# TaSCUD_ver02.net
KiCad netlist of a schematic drawn in EAGLE
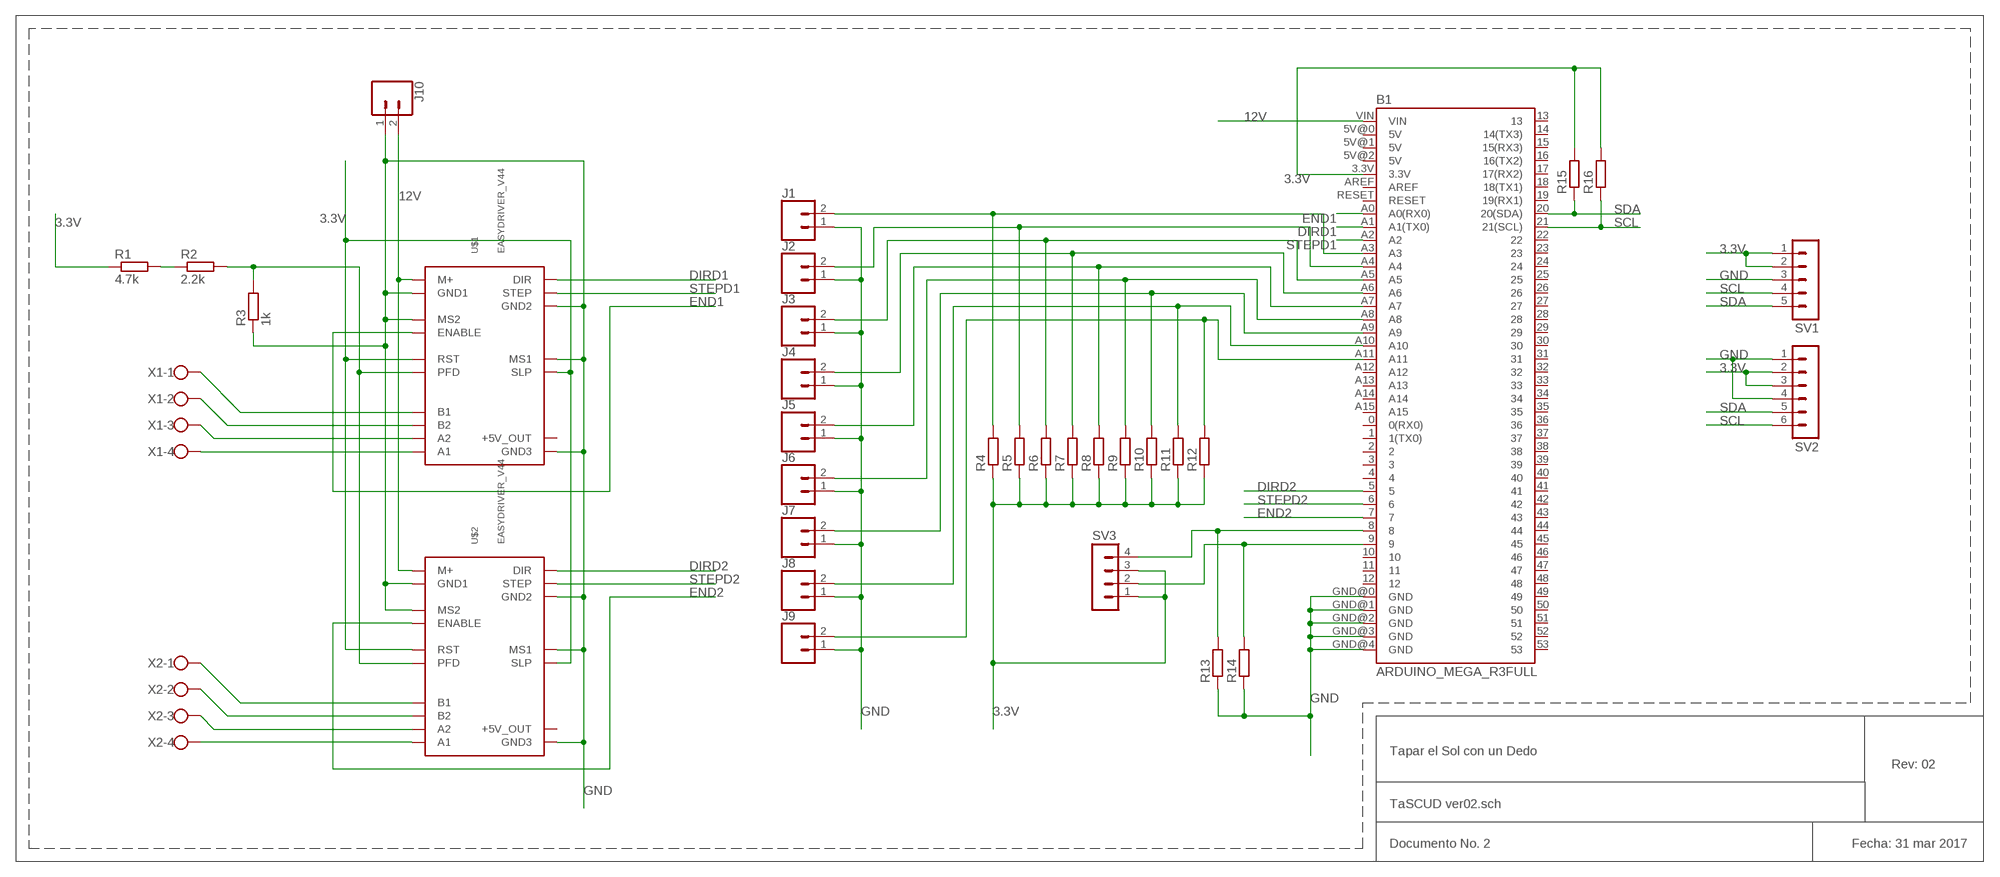
[diagram p0: schematic, sheet 1]

(export (version "E")
  (design (tool "Eeschema 10.0.6"))
  (components
    (comp (ref "B1")
      (value "ARDUINO_MEGA_R3FULL")
      (footprint "eagle-import:ARDUINO_MEGA")
      (libsource (lib "eagle-import") (part "ARDUINO_MEGA_R3FULL"))
    )
    (comp (ref "J1")
      (value "CONN_023.5MM-NO_SILK")
      (footprint "eagle-import:SCREWTERMINAL-3.5MM-2-NS")
      (libsource (lib "eagle-import") (part "CONN_023.5MM-NO_SILK"))
    )
    (comp (ref "J2")
      (value "CONN_023.5MM-NO_SILK")
      (footprint "eagle-import:SCREWTERMINAL-3.5MM-2-NS")
      (libsource (lib "eagle-import") (part "CONN_023.5MM-NO_SILK"))
    )
    (comp (ref "J3")
      (value "CONN_023.5MM-NO_SILK")
      (footprint "eagle-import:SCREWTERMINAL-3.5MM-2-NS")
      (libsource (lib "eagle-import") (part "CONN_023.5MM-NO_SILK"))
    )
    (comp (ref "J4")
      (value "CONN_023.5MM-NO_SILK")
      (footprint "eagle-import:SCREWTERMINAL-3.5MM-2-NS")
      (libsource (lib "eagle-import") (part "CONN_023.5MM-NO_SILK"))
    )
    (comp (ref "J5")
      (value "CONN_023.5MM-NO_SILK")
      (footprint "eagle-import:SCREWTERMINAL-3.5MM-2-NS")
      (libsource (lib "eagle-import") (part "CONN_023.5MM-NO_SILK"))
    )
    (comp (ref "J6")
      (value "CONN_023.5MM-NO_SILK")
      (footprint "eagle-import:SCREWTERMINAL-3.5MM-2-NS")
      (libsource (lib "eagle-import") (part "CONN_023.5MM-NO_SILK"))
    )
    (comp (ref "J7")
      (value "CONN_023.5MM-NO_SILK")
      (footprint "eagle-import:SCREWTERMINAL-3.5MM-2-NS")
      (libsource (lib "eagle-import") (part "CONN_023.5MM-NO_SILK"))
    )
    (comp (ref "J8")
      (value "CONN_023.5MM-NO_SILK")
      (footprint "eagle-import:SCREWTERMINAL-3.5MM-2-NS")
      (libsource (lib "eagle-import") (part "CONN_023.5MM-NO_SILK"))
    )
    (comp (ref "J9")
      (value "CONN_023.5MM-NO_SILK")
      (footprint "eagle-import:SCREWTERMINAL-3.5MM-2-NS")
      (libsource (lib "eagle-import") (part "CONN_023.5MM-NO_SILK"))
    )
    (comp (ref "J10")
      (value "CONN_023.5MM-NO_SILK")
      (footprint "eagle-import:SCREWTERMINAL-3.5MM-2-NS")
      (libsource (lib "eagle-import") (part "CONN_023.5MM-NO_SILK"))
    )
    (comp (ref "R1")
      (value "4.7k")
      (footprint "eagle-import:0204_7")
      (libsource (lib "eagle-import") (part "R-EU_0204/7"))
    )
    (comp (ref "R2")
      (value "2.2k")
      (footprint "eagle-import:0204_7")
      (libsource (lib "eagle-import") (part "R-EU_0204/7"))
    )
    (comp (ref "R3")
      (value "1k")
      (footprint "eagle-import:0204_7")
      (libsource (lib "eagle-import") (part "R-EU_0204/7"))
    )
    (comp (ref "R4")
      (value "R-EU_0204/7")
      (footprint "eagle-import:0204_7")
      (libsource (lib "eagle-import") (part "R-EU_0204/7"))
    )
    (comp (ref "R5")
      (value "R-EU_0204/7")
      (footprint "eagle-import:0204_7")
      (libsource (lib "eagle-import") (part "R-EU_0204/7"))
    )
    (comp (ref "R6")
      (value "R-EU_0204/7")
      (footprint "eagle-import:0204_7")
      (libsource (lib "eagle-import") (part "R-EU_0204/7"))
    )
    (comp (ref "R7")
      (value "R-EU_0204/7")
      (footprint "eagle-import:0204_7")
      (libsource (lib "eagle-import") (part "R-EU_0204/7"))
    )
    (comp (ref "R8")
      (value "R-EU_0204/7")
      (footprint "eagle-import:0204_7")
      (libsource (lib "eagle-import") (part "R-EU_0204/7"))
    )
    (comp (ref "R9")
      (value "R-EU_0204/7")
      (footprint "eagle-import:0204_7")
      (libsource (lib "eagle-import") (part "R-EU_0204/7"))
    )
    (comp (ref "R10")
      (value "R-EU_0204/7")
      (footprint "eagle-import:0204_7")
      (libsource (lib "eagle-import") (part "R-EU_0204/7"))
    )
    (comp (ref "R11")
      (value "R-EU_0204/7")
      (footprint "eagle-import:0204_7")
      (libsource (lib "eagle-import") (part "R-EU_0204/7"))
    )
    (comp (ref "R12")
      (value "R-EU_0204/7")
      (footprint "eagle-import:0204_7")
      (libsource (lib "eagle-import") (part "R-EU_0204/7"))
    )
    (comp (ref "R13")
      (value "R-EU_0204/7")
      (footprint "eagle-import:0204_7")
      (libsource (lib "eagle-import") (part "R-EU_0204/7"))
    )
    (comp (ref "R14")
      (value "R-EU_0204/7")
      (footprint "eagle-import:0204_7")
      (libsource (lib "eagle-import") (part "R-EU_0204/7"))
    )
    (comp (ref "R15")
      (value "R-EU_0204/7")
      (footprint "eagle-import:0204_7")
      (libsource (lib "eagle-import") (part "R-EU_0204/7"))
    )
    (comp (ref "R16")
      (value "R-EU_0204/7")
      (footprint "eagle-import:0204_7")
      (libsource (lib "eagle-import") (part "R-EU_0204/7"))
    )
    (comp (ref "SV1")
      (value "MA05-1")
      (footprint "eagle-import:MA05-1")
      (libsource (lib "eagle-import") (part "MA05-1"))
    )
    (comp (ref "SV2")
      (value "MA06-1")
      (footprint "eagle-import:MA06-1")
      (libsource (lib "eagle-import") (part "MA06-1"))
    )
    (comp (ref "SV3")
      (value "MA04-1")
      (footprint "eagle-import:MA04-1")
      (libsource (lib "eagle-import") (part "MA04-1"))
    )
    (comp (ref "U$1")
      (value "EASYDRIVER_V44")
      (footprint "eagle-import:EASYDRIVER_V44")
      (libsource (lib "eagle-import") (part "EASYDRIVER_V44"))
    )
    (comp (ref "U$2")
      (value "EASYDRIVER_V44")
      (footprint "eagle-import:EASYDRIVER_V44")
      (libsource (lib "eagle-import") (part "EASYDRIVER_V44"))
    )
    (comp (ref "X1")
      (value "W237-4")
      (footprint "eagle-import:W237-4")
      (libsource (lib "eagle-import") (part "W237-4"))
    )
    (comp (ref "X2")
      (value "W237-4")
      (footprint "eagle-import:W237-4")
      (libsource (lib "eagle-import") (part "W237-4"))
    )
  )
  (nets
    (net (code "1") (name "/3.3V") (class "Default")
      (node (ref "B1") (pin "3.3V") (pinfunction "3.3V_3.3V") (pintype "bidirectional"))
      (node (ref "R1") (pin "1") (pinfunction "1_1") (pintype "passive"))
      (node (ref "R10") (pin "1") (pinfunction "1_1") (pintype "passive"))
      (node (ref "R11") (pin "1") (pinfunction "1_1") (pintype "passive"))
      (node (ref "R12") (pin "1") (pinfunction "1_1") (pintype "passive"))
      (node (ref "R15") (pin "2") (pinfunction "2_2") (pintype "passive"))
      (node (ref "R16") (pin "2") (pinfunction "2_2") (pintype "passive"))
      (node (ref "R4") (pin "1") (pinfunction "1_1") (pintype "passive"))
      (node (ref "R5") (pin "1") (pinfunction "1_1") (pintype "passive"))
      (node (ref "R6") (pin "1") (pinfunction "1_1") (pintype "passive"))
      (node (ref "R7") (pin "1") (pinfunction "1_1") (pintype "passive"))
      (node (ref "R8") (pin "1") (pinfunction "1_1") (pintype "passive"))
      (node (ref "R9") (pin "1") (pinfunction "1_1") (pintype "passive"))
      (node (ref "SV1") (pin "1") (pinfunction "1_1") (pintype "passive"))
      (node (ref "SV1") (pin "2") (pinfunction "2_2") (pintype "passive"))
      (node (ref "SV2") (pin "2") (pinfunction "2_2") (pintype "passive"))
      (node (ref "SV2") (pin "3") (pinfunction "3_3") (pintype "passive"))
      (node (ref "SV3") (pin "1") (pinfunction "1_1") (pintype "passive"))
      (node (ref "SV3") (pin "3") (pinfunction "3_3") (pintype "passive"))
      (node (ref "U$1") (pin "RST") (pinfunction "RST_RST") (pintype "bidirectional"))
      (node (ref "U$1") (pin "SLEEP") (pinfunction "SLP_SLEEP") (pintype "bidirectional"))
      (node (ref "U$2") (pin "RST") (pinfunction "RST_RST") (pintype "bidirectional"))
      (node (ref "U$2") (pin "SLEEP") (pinfunction "SLP_SLEEP") (pintype "bidirectional"))
    )
    (net (code "2") (name "/12V") (class "Default")
      (node (ref "B1") (pin "VIN") (pinfunction "VIN_VIN") (pintype "bidirectional"))
      (node (ref "J10") (pin "2") (pinfunction "2_2") (pintype "passive"))
      (node (ref "U$1") (pin "M+") (pinfunction "M+_M+") (pintype "bidirectional"))
      (node (ref "U$2") (pin "M+") (pinfunction "M+_M+") (pintype "bidirectional"))
    )
    (net (code "3") (name "/DIRD1") (class "Default")
      (node (ref "B1") (pin "A1") (pinfunction "A1(TX0)_A1") (pintype "bidirectional"))
      (node (ref "U$1") (pin "DIR") (pinfunction "DIR_DIR") (pintype "bidirectional"))
    )
    (net (code "4") (name "/DIRD2") (class "Default")
      (node (ref "B1") (pin "5") (pinfunction "5_5") (pintype "bidirectional"))
      (node (ref "U$2") (pin "DIR") (pinfunction "DIR_DIR") (pintype "bidirectional"))
    )
    (net (code "5") (name "/END1") (class "Default")
      (node (ref "B1") (pin "A0") (pinfunction "A0(RX0)_A0") (pintype "bidirectional"))
      (node (ref "U$1") (pin "ENABLE") (pinfunction "ENABLE_ENABLE") (pintype "bidirectional"))
    )
    (net (code "6") (name "/END2") (class "Default")
      (node (ref "B1") (pin "7") (pinfunction "7_7") (pintype "bidirectional"))
      (node (ref "U$2") (pin "ENABLE") (pinfunction "ENABLE_ENABLE") (pintype "bidirectional"))
    )
    (net (code "7") (name "/GND") (class "Default")
      (node (ref "B1") (pin "GND@0") (pinfunction "GND_GND@0") (pintype "bidirectional"))
      (node (ref "B1") (pin "GND@1") (pinfunction "GND_GND@1") (pintype "bidirectional"))
      (node (ref "B1") (pin "GND@2") (pinfunction "GND_GND@2") (pintype "bidirectional"))
      (node (ref "B1") (pin "GND@3") (pinfunction "GND_GND@3") (pintype "bidirectional"))
      (node (ref "B1") (pin "GND@4") (pinfunction "GND_GND@4") (pintype "bidirectional"))
      (node (ref "J1") (pin "1") (pinfunction "1_1") (pintype "passive"))
      (node (ref "J10") (pin "1") (pinfunction "1_1") (pintype "passive"))
      (node (ref "J2") (pin "1") (pinfunction "1_1") (pintype "passive"))
      (node (ref "J3") (pin "1") (pinfunction "1_1") (pintype "passive"))
      (node (ref "J4") (pin "1") (pinfunction "1_1") (pintype "passive"))
      (node (ref "J5") (pin "1") (pinfunction "1_1") (pintype "passive"))
      (node (ref "J6") (pin "1") (pinfunction "1_1") (pintype "passive"))
      (node (ref "J7") (pin "1") (pinfunction "1_1") (pintype "passive"))
      (node (ref "J8") (pin "1") (pinfunction "1_1") (pintype "passive"))
      (node (ref "J9") (pin "1") (pinfunction "1_1") (pintype "passive"))
      (node (ref "R13") (pin "1") (pinfunction "1_1") (pintype "passive"))
      (node (ref "R14") (pin "1") (pinfunction "1_1") (pintype "passive"))
      (node (ref "R3") (pin "1") (pinfunction "1_1") (pintype "passive"))
      (node (ref "SV1") (pin "3") (pinfunction "3_3") (pintype "passive"))
      (node (ref "SV2") (pin "1") (pinfunction "1_1") (pintype "passive"))
      (node (ref "SV2") (pin "4") (pinfunction "4_4") (pintype "passive"))
      (node (ref "U$1") (pin "GND1") (pinfunction "GND1_GND1") (pintype "bidirectional"))
      (node (ref "U$1") (pin "GND2") (pinfunction "GND2_GND2") (pintype "bidirectional"))
      (node (ref "U$1") (pin "GND3") (pinfunction "GND3_GND3") (pintype "bidirectional"))
      (node (ref "U$1") (pin "MS1") (pinfunction "MS1_MS1") (pintype "bidirectional"))
      (node (ref "U$1") (pin "MS2") (pinfunction "MS2_MS2") (pintype "bidirectional"))
      (node (ref "U$2") (pin "GND1") (pinfunction "GND1_GND1") (pintype "bidirectional"))
      (node (ref "U$2") (pin "GND2") (pinfunction "GND2_GND2") (pintype "bidirectional"))
      (node (ref "U$2") (pin "GND3") (pinfunction "GND3_GND3") (pintype "bidirectional"))
      (node (ref "U$2") (pin "MS1") (pinfunction "MS1_MS1") (pintype "bidirectional"))
      (node (ref "U$2") (pin "MS2") (pinfunction "MS2_MS2") (pintype "bidirectional"))
    )
    (net (code "8") (name "/SCL") (class "Default")
      (node (ref "B1") (pin "21") (pinfunction "21(SCL)_21") (pintype "bidirectional"))
      (node (ref "R16") (pin "1") (pinfunction "1_1") (pintype "passive"))
      (node (ref "SV1") (pin "4") (pinfunction "4_4") (pintype "passive"))
      (node (ref "SV2") (pin "6") (pinfunction "6_6") (pintype "passive"))
    )
    (net (code "9") (name "/SDA") (class "Default")
      (node (ref "B1") (pin "20") (pinfunction "20(SDA)_20") (pintype "bidirectional"))
      (node (ref "R15") (pin "1") (pinfunction "1_1") (pintype "passive"))
      (node (ref "SV1") (pin "5") (pinfunction "5_5") (pintype "passive"))
      (node (ref "SV2") (pin "5") (pinfunction "5_5") (pintype "passive"))
    )
    (net (code "10") (name "/STEPD1") (class "Default")
      (node (ref "B1") (pin "A2") (pinfunction "A2_A2") (pintype "bidirectional"))
      (node (ref "U$1") (pin "STEP") (pinfunction "STEP_STEP") (pintype "bidirectional"))
    )
    (net (code "11") (name "/STEPD2") (class "Default")
      (node (ref "B1") (pin "6") (pinfunction "6_6") (pintype "bidirectional"))
      (node (ref "U$2") (pin "STEP") (pinfunction "STEP_STEP") (pintype "bidirectional"))
    )
    (net (code "12") (name "Net-(B1-Pad8)") (class "Default")
      (node (ref "B1") (pin "8") (pinfunction "8_8") (pintype "bidirectional"))
      (node (ref "R13") (pin "2") (pinfunction "2_2") (pintype "passive"))
      (node (ref "SV3") (pin "4") (pinfunction "4_4") (pintype "passive"))
    )
    (net (code "13") (name "Net-(B1-Pad9)") (class "Default")
      (node (ref "B1") (pin "9") (pinfunction "9_9") (pintype "bidirectional"))
      (node (ref "R14") (pin "2") (pinfunction "2_2") (pintype "passive"))
      (node (ref "SV3") (pin "2") (pinfunction "2_2") (pintype "passive"))
    )
    (net (code "14") (name "Net-(B1-PadA3)") (class "Default")
      (node (ref "B1") (pin "A3") (pinfunction "A3_A3") (pintype "bidirectional"))
      (node (ref "J1") (pin "2") (pinfunction "2_2") (pintype "passive"))
      (node (ref "R4") (pin "2") (pinfunction "2_2") (pintype "passive"))
    )
    (net (code "15") (name "Net-(B1-PadA4)") (class "Default")
      (node (ref "B1") (pin "A4") (pinfunction "A4_A4") (pintype "bidirectional"))
      (node (ref "J2") (pin "2") (pinfunction "2_2") (pintype "passive"))
      (node (ref "R5") (pin "2") (pinfunction "2_2") (pintype "passive"))
    )
    (net (code "16") (name "Net-(B1-PadA5)") (class "Default")
      (node (ref "B1") (pin "A5") (pinfunction "A5_A5") (pintype "bidirectional"))
      (node (ref "J3") (pin "2") (pinfunction "2_2") (pintype "passive"))
      (node (ref "R6") (pin "2") (pinfunction "2_2") (pintype "passive"))
    )
    (net (code "17") (name "Net-(B1-PadA6)") (class "Default")
      (node (ref "B1") (pin "A6") (pinfunction "A6_A6") (pintype "bidirectional"))
      (node (ref "J4") (pin "2") (pinfunction "2_2") (pintype "passive"))
      (node (ref "R7") (pin "2") (pinfunction "2_2") (pintype "passive"))
    )
    (net (code "18") (name "Net-(B1-PadA7)") (class "Default")
      (node (ref "B1") (pin "A7") (pinfunction "A7_A7") (pintype "bidirectional"))
      (node (ref "J5") (pin "2") (pinfunction "2_2") (pintype "passive"))
      (node (ref "R8") (pin "2") (pinfunction "2_2") (pintype "passive"))
    )
    (net (code "19") (name "Net-(B1-PadA8)") (class "Default")
      (node (ref "B1") (pin "A8") (pinfunction "A8_A8") (pintype "bidirectional"))
      (node (ref "J6") (pin "2") (pinfunction "2_2") (pintype "passive"))
      (node (ref "R9") (pin "2") (pinfunction "2_2") (pintype "passive"))
    )
    (net (code "20") (name "Net-(B1-PadA9)") (class "Default")
      (node (ref "B1") (pin "A9") (pinfunction "A9_A9") (pintype "bidirectional"))
      (node (ref "J7") (pin "2") (pinfunction "2_2") (pintype "passive"))
      (node (ref "R10") (pin "2") (pinfunction "2_2") (pintype "passive"))
    )
    (net (code "21") (name "Net-(B1-PadA10)") (class "Default")
      (node (ref "B1") (pin "A10") (pinfunction "A10_A10") (pintype "bidirectional"))
      (node (ref "J8") (pin "2") (pinfunction "2_2") (pintype "passive"))
      (node (ref "R11") (pin "2") (pinfunction "2_2") (pintype "passive"))
    )
    (net (code "22") (name "Net-(B1-PadA11)") (class "Default")
      (node (ref "B1") (pin "A11") (pinfunction "A11_A11") (pintype "bidirectional"))
      (node (ref "J9") (pin "2") (pinfunction "2_2") (pintype "passive"))
      (node (ref "R12") (pin "2") (pinfunction "2_2") (pintype "passive"))
    )
    (net (code "23") (name "Net-(R1-Pad2)") (class "Default")
      (node (ref "R1") (pin "2") (pinfunction "2_2") (pintype "passive"))
      (node (ref "R2") (pin "1") (pinfunction "1_1") (pintype "passive"))
    )
    (net (code "24") (name "Net-(R2-Pad2)") (class "Default")
      (node (ref "R2") (pin "2") (pinfunction "2_2") (pintype "passive"))
      (node (ref "R3") (pin "2") (pinfunction "2_2") (pintype "passive"))
      (node (ref "U$1") (pin "PFD") (pinfunction "PFD_PFD") (pintype "bidirectional"))
      (node (ref "U$2") (pin "PFD") (pinfunction "PFD_PFD") (pintype "bidirectional"))
    )
    (net (code "25") (name "Net-(X1A-KL)") (class "Default")
      (node (ref "U$1") (pin "B1") (pinfunction "B1_B1") (pintype "bidirectional"))
      (node (ref "X1") (pin "1") (pinfunction "KL_1") (pintype "passive"))
    )
    (net (code "26") (name "Net-(X1B-KL)") (class "Default")
      (node (ref "U$1") (pin "B2") (pinfunction "B2_B2") (pintype "bidirectional"))
      (node (ref "X1") (pin "2") (pinfunction "KL_2") (pintype "passive"))
    )
    (net (code "27") (name "Net-(X1C-KL)") (class "Default")
      (node (ref "U$1") (pin "A2") (pinfunction "A2_A2") (pintype "bidirectional"))
      (node (ref "X1") (pin "3") (pinfunction "KL_3") (pintype "passive"))
    )
    (net (code "28") (name "Net-(X1D-KL)") (class "Default")
      (node (ref "U$1") (pin "A1") (pinfunction "A1_A1") (pintype "bidirectional"))
      (node (ref "X1") (pin "4") (pinfunction "KL_4") (pintype "passive"))
    )
    (net (code "29") (name "Net-(X2A-KL)") (class "Default")
      (node (ref "U$2") (pin "B1") (pinfunction "B1_B1") (pintype "bidirectional"))
      (node (ref "X2") (pin "1") (pinfunction "KL_1") (pintype "passive"))
    )
    (net (code "30") (name "Net-(X2B-KL)") (class "Default")
      (node (ref "U$2") (pin "B2") (pinfunction "B2_B2") (pintype "bidirectional"))
      (node (ref "X2") (pin "2") (pinfunction "KL_2") (pintype "passive"))
    )
    (net (code "31") (name "Net-(X2C-KL)") (class "Default")
      (node (ref "U$2") (pin "A2") (pinfunction "A2_A2") (pintype "bidirectional"))
      (node (ref "X2") (pin "3") (pinfunction "KL_3") (pintype "passive"))
    )
    (net (code "32") (name "Net-(X2D-KL)") (class "Default")
      (node (ref "U$2") (pin "A1") (pinfunction "A1_A1") (pintype "bidirectional"))
      (node (ref "X2") (pin "4") (pinfunction "KL_4") (pintype "passive"))
    )
    (net (code "33") (name "unconnected-(B1-0(RX0)-Pad0)") (class "Default")
      (node (ref "B1") (pin "0") (pinfunction "0(RX0)_0") (pintype "bidirectional"))
    )
    (net (code "34") (name "unconnected-(B1-1(TX0)-Pad1)") (class "Default")
      (node (ref "B1") (pin "1") (pinfunction "1(TX0)_1") (pintype "bidirectional"))
    )
    (net (code "35") (name "unconnected-(B1-5V-Pad5V@0)") (class "Default")
      (node (ref "B1") (pin "5V@0") (pinfunction "5V_5V@0") (pintype "bidirectional"))
    )
    (net (code "36") (name "unconnected-(B1-5V-Pad5V@1)") (class "Default")
      (node (ref "B1") (pin "5V@1") (pinfunction "5V_5V@1") (pintype "bidirectional"))
    )
    (net (code "37") (name "unconnected-(B1-5V-Pad5V@2)") (class "Default")
      (node (ref "B1") (pin "5V@2") (pinfunction "5V_5V@2") (pintype "bidirectional"))
    )
    (net (code "38") (name "unconnected-(B1-14(TX3)-Pad14)") (class "Default")
      (node (ref "B1") (pin "14") (pinfunction "14(TX3)_14") (pintype "bidirectional"))
    )
    (net (code "39") (name "unconnected-(B1-15(RX3)-Pad15)") (class "Default")
      (node (ref "B1") (pin "15") (pinfunction "15(RX3)_15") (pintype "bidirectional"))
    )
    (net (code "40") (name "unconnected-(B1-16(TX2)-Pad16)") (class "Default")
      (node (ref "B1") (pin "16") (pinfunction "16(TX2)_16") (pintype "bidirectional"))
    )
    (net (code "41") (name "unconnected-(B1-17(RX2)-Pad17)") (class "Default")
      (node (ref "B1") (pin "17") (pinfunction "17(RX2)_17") (pintype "bidirectional"))
    )
    (net (code "42") (name "unconnected-(B1-18(TX1)-Pad18)") (class "Default")
      (node (ref "B1") (pin "18") (pinfunction "18(TX1)_18") (pintype "bidirectional"))
    )
    (net (code "43") (name "unconnected-(B1-19(RX1)-Pad19)") (class "Default")
      (node (ref "B1") (pin "19") (pinfunction "19(RX1)_19") (pintype "bidirectional"))
    )
    (net (code "44") (name "unconnected-(B1-Pad2)") (class "Default")
      (node (ref "B1") (pin "2") (pinfunction "2_2") (pintype "bidirectional"))
    )
    (net (code "45") (name "unconnected-(B1-Pad3)") (class "Default")
      (node (ref "B1") (pin "3") (pinfunction "3_3") (pintype "bidirectional"))
    )
    (net (code "46") (name "unconnected-(B1-Pad4)") (class "Default")
      (node (ref "B1") (pin "4") (pinfunction "4_4") (pintype "bidirectional"))
    )
    (net (code "47") (name "unconnected-(B1-Pad10)") (class "Default")
      (node (ref "B1") (pin "10") (pinfunction "10_10") (pintype "bidirectional"))
    )
    (net (code "48") (name "unconnected-(B1-Pad11)") (class "Default")
      (node (ref "B1") (pin "11") (pinfunction "11_11") (pintype "bidirectional"))
    )
    (net (code "49") (name "unconnected-(B1-Pad12)") (class "Default")
      (node (ref "B1") (pin "12") (pinfunction "12_12") (pintype "bidirectional"))
    )
    (net (code "50") (name "unconnected-(B1-Pad13)") (class "Default")
      (node (ref "B1") (pin "13") (pinfunction "13_13") (pintype "bidirectional"))
    )
    (net (code "51") (name "unconnected-(B1-Pad22)") (class "Default")
      (node (ref "B1") (pin "22") (pinfunction "22_22") (pintype "bidirectional"))
    )
    (net (code "52") (name "unconnected-(B1-Pad23)") (class "Default")
      (node (ref "B1") (pin "23") (pinfunction "23_23") (pintype "bidirectional"))
    )
    (net (code "53") (name "unconnected-(B1-Pad24)") (class "Default")
      (node (ref "B1") (pin "24") (pinfunction "24_24") (pintype "bidirectional"))
    )
    (net (code "54") (name "unconnected-(B1-Pad25)") (class "Default")
      (node (ref "B1") (pin "25") (pinfunction "25_25") (pintype "bidirectional"))
    )
    (net (code "55") (name "unconnected-(B1-Pad26)") (class "Default")
      (node (ref "B1") (pin "26") (pinfunction "26_26") (pintype "bidirectional"))
    )
    (net (code "56") (name "unconnected-(B1-Pad27)") (class "Default")
      (node (ref "B1") (pin "27") (pinfunction "27_27") (pintype "bidirectional"))
    )
    (net (code "57") (name "unconnected-(B1-Pad28)") (class "Default")
      (node (ref "B1") (pin "28") (pinfunction "28_28") (pintype "bidirectional"))
    )
    (net (code "58") (name "unconnected-(B1-Pad29)") (class "Default")
      (node (ref "B1") (pin "29") (pinfunction "29_29") (pintype "bidirectional"))
    )
    (net (code "59") (name "unconnected-(B1-Pad30)") (class "Default")
      (node (ref "B1") (pin "30") (pinfunction "30_30") (pintype "bidirectional"))
    )
    (net (code "60") (name "unconnected-(B1-Pad31)") (class "Default")
      (node (ref "B1") (pin "31") (pinfunction "31_31") (pintype "bidirectional"))
    )
    (net (code "61") (name "unconnected-(B1-Pad32)") (class "Default")
      (node (ref "B1") (pin "32") (pinfunction "32_32") (pintype "bidirectional"))
    )
    (net (code "62") (name "unconnected-(B1-Pad33)") (class "Default")
      (node (ref "B1") (pin "33") (pinfunction "33_33") (pintype "bidirectional"))
    )
    (net (code "63") (name "unconnected-(B1-Pad34)") (class "Default")
      (node (ref "B1") (pin "34") (pinfunction "34_34") (pintype "bidirectional"))
    )
    (net (code "64") (name "unconnected-(B1-Pad35)") (class "Default")
      (node (ref "B1") (pin "35") (pinfunction "35_35") (pintype "bidirectional"))
    )
    (net (code "65") (name "unconnected-(B1-Pad36)") (class "Default")
      (node (ref "B1") (pin "36") (pinfunction "36_36") (pintype "bidirectional"))
    )
    (net (code "66") (name "unconnected-(B1-Pad37)") (class "Default")
      (node (ref "B1") (pin "37") (pinfunction "37_37") (pintype "bidirectional"))
    )
    (net (code "67") (name "unconnected-(B1-Pad38)") (class "Default")
      (node (ref "B1") (pin "38") (pinfunction "38_38") (pintype "bidirectional"))
    )
    (net (code "68") (name "unconnected-(B1-Pad39)") (class "Default")
      (node (ref "B1") (pin "39") (pinfunction "39_39") (pintype "bidirectional"))
    )
    (net (code "69") (name "unconnected-(B1-Pad40)") (class "Default")
      (node (ref "B1") (pin "40") (pinfunction "40_40") (pintype "bidirectional"))
    )
    (net (code "70") (name "unconnected-(B1-Pad41)") (class "Default")
      (node (ref "B1") (pin "41") (pinfunction "41_41") (pintype "bidirectional"))
    )
    (net (code "71") (name "unconnected-(B1-Pad42)") (class "Default")
      (node (ref "B1") (pin "42") (pinfunction "42_42") (pintype "bidirectional"))
    )
    (net (code "72") (name "unconnected-(B1-Pad43)") (class "Default")
      (node (ref "B1") (pin "43") (pinfunction "43_43") (pintype "bidirectional"))
    )
    (net (code "73") (name "unconnected-(B1-Pad44)") (class "Default")
      (node (ref "B1") (pin "44") (pinfunction "44_44") (pintype "bidirectional"))
    )
    (net (code "74") (name "unconnected-(B1-Pad45)") (class "Default")
      (node (ref "B1") (pin "45") (pinfunction "45_45") (pintype "bidirectional"))
    )
    (net (code "75") (name "unconnected-(B1-Pad46)") (class "Default")
      (node (ref "B1") (pin "46") (pinfunction "46_46") (pintype "bidirectional"))
    )
    (net (code "76") (name "unconnected-(B1-Pad47)") (class "Default")
      (node (ref "B1") (pin "47") (pinfunction "47_47") (pintype "bidirectional"))
    )
    (net (code "77") (name "unconnected-(B1-Pad48)") (class "Default")
      (node (ref "B1") (pin "48") (pinfunction "48_48") (pintype "bidirectional"))
    )
    (net (code "78") (name "unconnected-(B1-Pad49)") (class "Default")
      (node (ref "B1") (pin "49") (pinfunction "49_49") (pintype "bidirectional"))
    )
    (net (code "79") (name "unconnected-(B1-Pad50)") (class "Default")
      (node (ref "B1") (pin "50") (pinfunction "50_50") (pintype "bidirectional"))
    )
    (net (code "80") (name "unconnected-(B1-Pad51)") (class "Default")
      (node (ref "B1") (pin "51") (pinfunction "51_51") (pintype "bidirectional"))
    )
    (net (code "81") (name "unconnected-(B1-Pad52)") (class "Default")
      (node (ref "B1") (pin "52") (pinfunction "52_52") (pintype "bidirectional"))
    )
    (net (code "82") (name "unconnected-(B1-Pad53)") (class "Default")
      (node (ref "B1") (pin "53") (pinfunction "53_53") (pintype "bidirectional"))
    )
    (net (code "83") (name "unconnected-(B1-PadA12)") (class "Default")
      (node (ref "B1") (pin "A12") (pinfunction "A12_A12") (pintype "bidirectional"))
    )
    (net (code "84") (name "unconnected-(B1-PadA13)") (class "Default")
      (node (ref "B1") (pin "A13") (pinfunction "A13_A13") (pintype "bidirectional"))
    )
    (net (code "85") (name "unconnected-(B1-PadA14)") (class "Default")
      (node (ref "B1") (pin "A14") (pinfunction "A14_A14") (pintype "bidirectional"))
    )
    (net (code "86") (name "unconnected-(B1-PadA15)") (class "Default")
      (node (ref "B1") (pin "A15") (pinfunction "A15_A15") (pintype "bidirectional"))
    )
    (net (code "87") (name "unconnected-(B1-PadAREF)") (class "Default")
      (node (ref "B1") (pin "AREF") (pinfunction "AREF_AREF") (pintype "bidirectional"))
    )
    (net (code "88") (name "unconnected-(B1-PadRESET)") (class "Default")
      (node (ref "B1") (pin "RESET") (pinfunction "RESET_RESET") (pintype "bidirectional"))
    )
    (net (code "89") (name "unconnected-(U$1-+5V_OUT-PadP$11)") (class "Default")
      (node (ref "U$1") (pin "P$11") (pinfunction "+5V_OUT_P$11") (pintype "bidirectional"))
    )
    (net (code "90") (name "unconnected-(U$2-+5V_OUT-PadP$11)") (class "Default")
      (node (ref "U$2") (pin "P$11") (pinfunction "+5V_OUT_P$11") (pintype "bidirectional"))
    )
  )
)
